# Main.net
KiCad netlist of a schematic drawn in Altium Designer
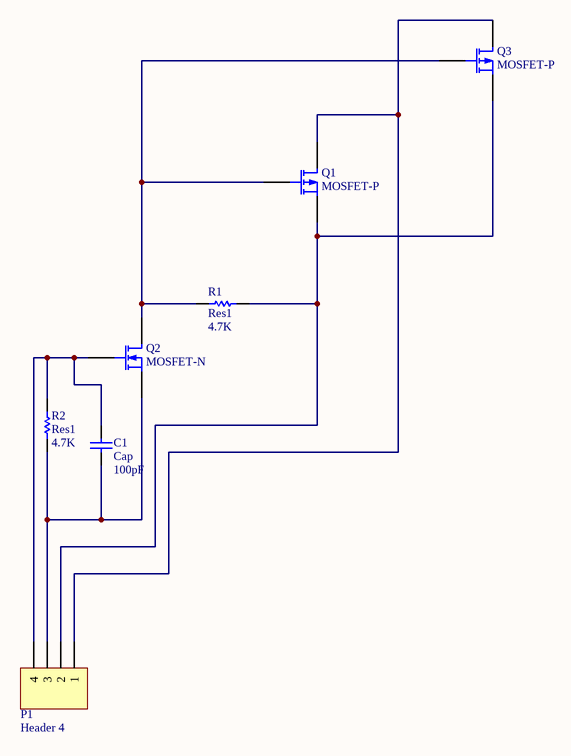
[diagram p0: Main.SchDoc]

(export (version "E")
  (design (tool "Eeschema 10.0.6"))
  (components
    (comp (ref "C1")
      (value "Cap")
      (footprint "Switch:0603")
      (description "Capacitor")
      (fields (field (name "ALTIUM_VALUE") "100pF") (field (name "PUBLISHER") "Altium Limited"))
      (libsource (lib "Miscellaneous Devices") (part "Cap"))
    )
    (comp (ref "P1")
      (value "Header 4")
      (footprint "HDR1X4")
      (description "Header, 4-Pin")
      (fields (field (name "PUBLISHER") "Altium Limited"))
      (libsource (lib "Miscellaneous Connectors") (part "Header 4"))
    )
    (comp (ref "Q1")
      (value "MOSFET-P")
      (footprint "Switch:SOT23-3-PMOS")
      (description "P-Channel MOSFET")
      (fields (field (name "PUBLISHER") "Altium Limited"))
      (libsource (lib "Miscellaneous Devices") (part "MOSFET-P"))
    )
    (comp (ref "Q2")
      (value "MOSFET-N")
      (footprint "Switch:SOT23-3-PMOS")
      (description "N-Channel MOSFET")
      (fields (field (name "PUBLISHER") "Altium Limited"))
      (libsource (lib "Miscellaneous Devices") (part "MOSFET-N"))
    )
    (comp (ref "Q3")
      (value "MOSFET-P")
      (footprint "Switch:D2PAK")
      (description "P-Channel MOSFET")
      (fields (field (name "PUBLISHER") "Altium Limited"))
      (libsource (lib "Miscellaneous Devices") (part "MOSFET-P"))
    )
    (comp (ref "R1")
      (value "Res1")
      (footprint "Switch:0603")
      (description "Resistor")
      (fields (field (name "ALTIUM_VALUE") "4.7K") (field (name "PUBLISHER") "Altium Limited"))
      (libsource (lib "Miscellaneous Devices") (part "Res1"))
    )
    (comp (ref "R2")
      (value "Res1")
      (footprint "Switch:0603")
      (description "Resistor")
      (fields (field (name "ALTIUM_VALUE") "4.7K") (field (name "PUBLISHER") "Altium Limited"))
      (libsource (lib "Miscellaneous Devices") (part "Res1"))
    )
  )
  (nets
    (net (code "1") (name "Net-(Q1-D)") (class "Default")
      (node (ref "P1") (pin "1") (pinfunction "1_1") (pintype "passive"))
      (node (ref "Q1") (pin "1") (pinfunction "D_1") (pintype "passive"))
      (node (ref "Q3") (pin "1") (pinfunction "D_1") (pintype "passive"))
    )
    (net (code "2") (name "Net-(Q1-G)") (class "Default")
      (node (ref "Q1") (pin "2") (pinfunction "G_2") (pintype "passive"))
      (node (ref "Q2") (pin "1") (pinfunction "D_1") (pintype "passive"))
      (node (ref "Q3") (pin "2") (pinfunction "G_2") (pintype "passive"))
      (node (ref "R1") (pin "2") (pinfunction "2_2") (pintype "passive"))
    )
    (net (code "3") (name "Net-(Q1-S)") (class "Default")
      (node (ref "P1") (pin "2") (pinfunction "2_2") (pintype "passive"))
      (node (ref "Q1") (pin "3") (pinfunction "S_3") (pintype "passive"))
      (node (ref "Q3") (pin "3") (pinfunction "S_3") (pintype "passive"))
      (node (ref "R1") (pin "1") (pinfunction "1_1") (pintype "passive"))
    )
    (net (code "4") (name "Net-(Q2-G)") (class "Default")
      (node (ref "C1") (pin "2") (pinfunction "2_2") (pintype "passive"))
      (node (ref "P1") (pin "4") (pinfunction "4_4") (pintype "passive"))
      (node (ref "Q2") (pin "2") (pinfunction "G_2") (pintype "passive"))
      (node (ref "R2") (pin "2") (pinfunction "2_2") (pintype "passive"))
    )
    (net (code "5") (name "Net-(Q2-S)") (class "Default")
      (node (ref "C1") (pin "1") (pinfunction "1_1") (pintype "passive"))
      (node (ref "P1") (pin "3") (pinfunction "3_3") (pintype "passive"))
      (node (ref "Q2") (pin "3") (pinfunction "S_3") (pintype "passive"))
      (node (ref "R2") (pin "1") (pinfunction "1_1") (pintype "passive"))
    )
  )
)
